# power-supply.net
KiCad netlist of a schematic drawn in Altium Designer
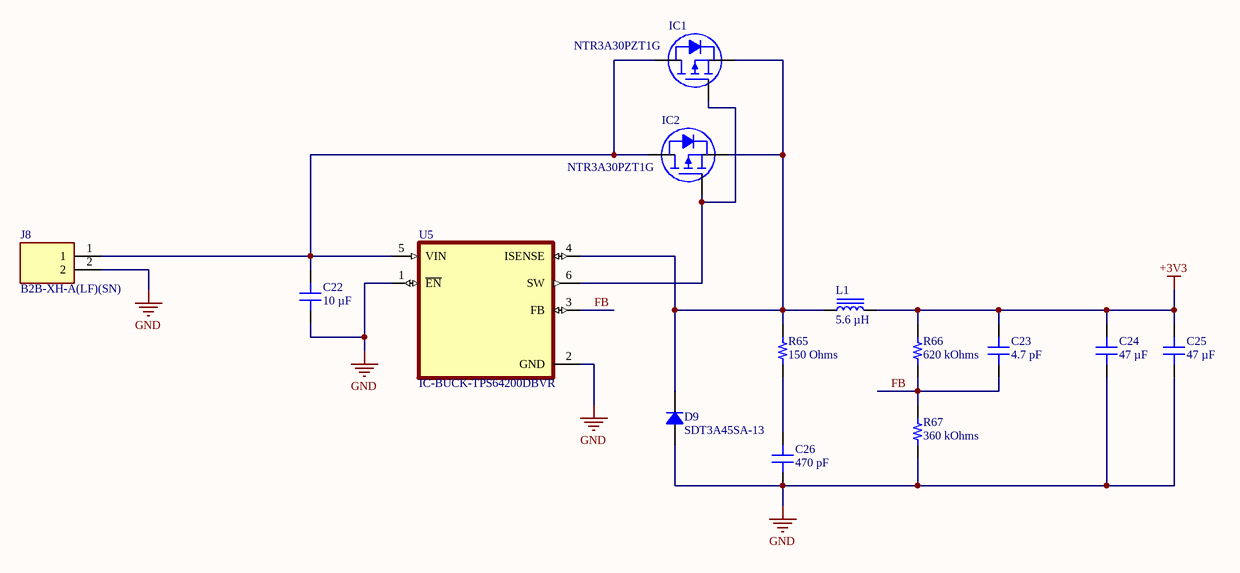
[diagram p0: power-supply.SchDoc]

(export (version "E")
  (design (tool "Eeschema 10.0.6"))
  (components
    (comp (ref "C22")
      (value "10 µF")
      (footprint "CAP 1206_3216 - 0.8MM")
      (description "CAP CER 10UF 16V X5R 1206")
      (fields (field (name "PART NUMBER") "EMK316BJ106MD-T") (field (name "MANUFACTURER") "Taiyo Yuden"))
      (libsource (lib "CAL") (part "Capacitor"))
    )
    (comp (ref "C23")
      (value "4.7 pF")
      (footprint "CAP 0603_1608")
      (description "CAP CER 4.7PF 250V C0G/NP0 0603")
      (fields
        (field (name "PART NUMBER") "600S4R7CT250XT")
        (field (name "MANUFACTURER") "American Technical Ceramics")
      )
      (libsource (lib "CAL") (part "Capacitor"))
    )
    (comp (ref "C24")
      (value "47 µF")
      (footprint "CAP 0603_1608")
      (description "CAP CER 47UF 4V X5R 0603")
      (fields
        (field (name "PART NUMBER") "CL10A476MR8NZNE")
        (field (name "MANUFACTURER") "Samsung Electro-Mechanics")
      )
      (libsource (lib "CAL") (part "Capacitor"))
    )
    (comp (ref "C25")
      (value "47 µF")
      (footprint "CAP 1206_3216 - 0.8MM")
      (description "CAP CER 47UF 6.3V X7S 1206")
      (fields
        (field (name "PART NUMBER") "C3216X7S0J476M160AC")
        (field (name "MANUFACTURER") "TDK Corporation")
      )
      (libsource (lib "CAL") (part "Capacitor"))
    )
    (comp (ref "C26")
      (value "470 pF")
      (footprint "CAP 0603_1608")
      (description "CAP CER 470PF 25V C0G/NP0 0603")
      (fields (field (name "PART NUMBER") "C0603C471J3GACAUTO") (field (name "MANUFACTURER") "KEMET"))
      (libsource (lib "CAL") (part "Capacitor"))
    )
    (comp (ref "D9")
      (value "SDT3A45SA-13")
      (footprint "DO214AC SMA")
      (description "SCHOTTKY RECTIFIER SMA T&R 10K")
      (fields (field (name "MANUFACTURER") "Diodes Incorporated"))
      (libsource (lib "CAL") (part "Diode"))
    )
    (comp (ref "IC1")
      (value "NTR3A30PZT1G")
      (footprint "ON SEMI SOT-23-3")
      (description "MOSFET P-CH 20V 3A SOT23")
      (fields (field (name "MANUFACTURER") "ON Semiconductor"))
      (libsource (lib "CAL") (part "ON SEMI MOSFET P-CH SOT-23-3"))
    )
    (comp (ref "IC2")
      (value "NTR3A30PZT1G")
      (footprint "ON SEMI SOT-23-3")
      (description "MOSFET P-CH 20V 3A SOT23")
      (fields (field (name "MANUFACTURER") "ON Semiconductor"))
      (libsource (lib "CAL") (part "ON SEMI MOSFET P-CH SOT-23-3"))
    )
    (comp (ref "J8")
      (value "B2B-XH-A(LF)(SN)")
      (footprint "JST_B2B-XH-A(LF)(SN)")
      (description "Connector Header Through Hole 2 position 0.098\" (2.50mm)")
      (fields (field (name "MF") "{'manufacturer': u'JST Sales'}"))
      (libsource (lib "extra_components") (part "B2B-XH-A(LF)(SN)"))
    )
    (comp (ref "L1")
      (value "5.6 µH")
      (footprint "BOURNS SRP5030T")
      (description "FIXED IND 5.6UH 4.25A 63MOHM SMD")
      (fields (field (name "PART NUMBER") "SRP5030T-5R6M") (field (name "MANUFACTURER") "Bourns Inc."))
      (libsource (lib "CAL") (part "Inductor"))
    )
    (comp (ref "R65")
      (value "150 Ohms")
      (footprint "RES 1206_3216")
      (description "RES SMD 150 OHM 0.1% 1/4W 1206")
      (fields (field (name "PART NUMBER") "RT1206BRD07150RL") (field (name "MANUFACTURER") "Yageo"))
      (libsource (lib "CAL") (part "Resistor"))
    )
    (comp (ref "R66")
      (value "620 kOhms")
      (footprint "RES 0805_2012")
      (description "RES 620K OHM 5% 1/8W 0805")
      (fields
        (field (name "PART NUMBER") "RMCF0805JT620K")
        (field (name "MANUFACTURER") "Stackpole Electronics Inc")
      )
      (libsource (lib "CAL") (part "Resistor"))
    )
    (comp (ref "R67")
      (value "360 kOhms")
      (footprint "RES 0805_2012")
      (description "RES 360K OHM 5% 1/8W 0805")
      (fields (field (name "PART NUMBER") "RC0805JR-07360KL") (field (name "MANUFACTURER") "Yageo"))
      (libsource (lib "CAL") (part "Resistor"))
    )
    (comp (ref "U5")
      (value "IC-BUCK-TPS64200DBVR")
      (footprint "IC-BUCK-TPS64200DBVR-SOT95P280X145-6N")
      (description "1.8 to 6.5 V input, 350 kHz, 95% efficient step-down controller, 20 uA, SOT-23 6-SOT-23 -40 to 85")
      (fields (field (name "MP") "TPS64200DBVR") (field (name "MF") "Texas Instruments"))
      (libsource (lib "extra_components") (part "IC-BUCK-TPS64200DBVR"))
    )
  )
  (nets
    (net (code "1") (name "+3V3") (class "Default")
      (node (ref "C23") (pin "2") (pinfunction "2_2") (pintype "passive"))
      (node (ref "C24") (pin "2") (pinfunction "2_2") (pintype "passive"))
      (node (ref "C25") (pin "2") (pinfunction "2_2") (pintype "passive"))
      (node (ref "L1") (pin "2") (pinfunction "2_2") (pintype "passive"))
      (node (ref "R66") (pin "2") (pinfunction "2_2") (pintype "passive"))
    )
    (net (code "2") (name "/FB") (class "Default")
      (node (ref "C23") (pin "1") (pinfunction "1_1") (pintype "passive"))
      (node (ref "R66") (pin "1") (pinfunction "1_1") (pintype "passive"))
      (node (ref "R67") (pin "2") (pinfunction "2_2") (pintype "passive"))
      (node (ref "U5") (pin "3") (pinfunction "FB_3") (pintype "bidirectional"))
    )
    (net (code "3") (name "GND") (class "Default")
      (node (ref "C22") (pin "1") (pinfunction "1_1") (pintype "passive"))
      (node (ref "C24") (pin "1") (pinfunction "1_1") (pintype "passive"))
      (node (ref "C25") (pin "1") (pinfunction "1_1") (pintype "passive"))
      (node (ref "C26") (pin "1") (pinfunction "1_1") (pintype "passive"))
      (node (ref "D9") (pin "1") (pinfunction "1_1") (pintype "passive"))
      (node (ref "J8") (pin "2") (pinfunction "2_2") (pintype "passive"))
      (node (ref "R67") (pin "1") (pinfunction "1_1") (pintype "passive"))
      (node (ref "U5") (pin "1") (pinfunction "~{EN}_1") (pintype "bidirectional"))
      (node (ref "U5") (pin "2") (pinfunction "GND_2") (pintype "power_in"))
    )
    (net (code "4") (name "Net-(C26-Pad2)") (class "Default")
      (node (ref "C26") (pin "2") (pinfunction "2_2") (pintype "passive"))
      (node (ref "R65") (pin "1") (pinfunction "1_1") (pintype "passive"))
    )
    (net (code "5") (name "Net-(IC1-D)") (class "Default")
      (node (ref "C22") (pin "2") (pinfunction "2_2") (pintype "passive"))
      (node (ref "IC1") (pin "3") (pinfunction "D_3") (pintype "passive"))
      (node (ref "IC2") (pin "3") (pinfunction "D_3") (pintype "passive"))
      (node (ref "J8") (pin "1") (pinfunction "1_1") (pintype "passive"))
      (node (ref "U5") (pin "5") (pinfunction "VIN_5") (pintype "input"))
    )
    (net (code "6") (name "Net-(IC1-G)") (class "Default")
      (node (ref "IC1") (pin "1") (pinfunction "G_1") (pintype "passive"))
      (node (ref "IC2") (pin "1") (pinfunction "G_1") (pintype "passive"))
      (node (ref "U5") (pin "6") (pinfunction "SW_6") (pintype "output"))
    )
    (net (code "7") (name "Net-(IC1-S)") (class "Default")
      (node (ref "D9") (pin "2") (pinfunction "2_2") (pintype "passive"))
      (node (ref "IC1") (pin "2") (pinfunction "S_2") (pintype "passive"))
      (node (ref "IC2") (pin "2") (pinfunction "S_2") (pintype "passive"))
      (node (ref "L1") (pin "1") (pinfunction "1_1") (pintype "passive"))
      (node (ref "R65") (pin "2") (pinfunction "2_2") (pintype "passive"))
      (node (ref "U5") (pin "4") (pinfunction "ISENSE_4") (pintype "bidirectional"))
    )
  )
)
